# CS4398_DAC.net
KiCad netlist of a schematic drawn in Altium Designer
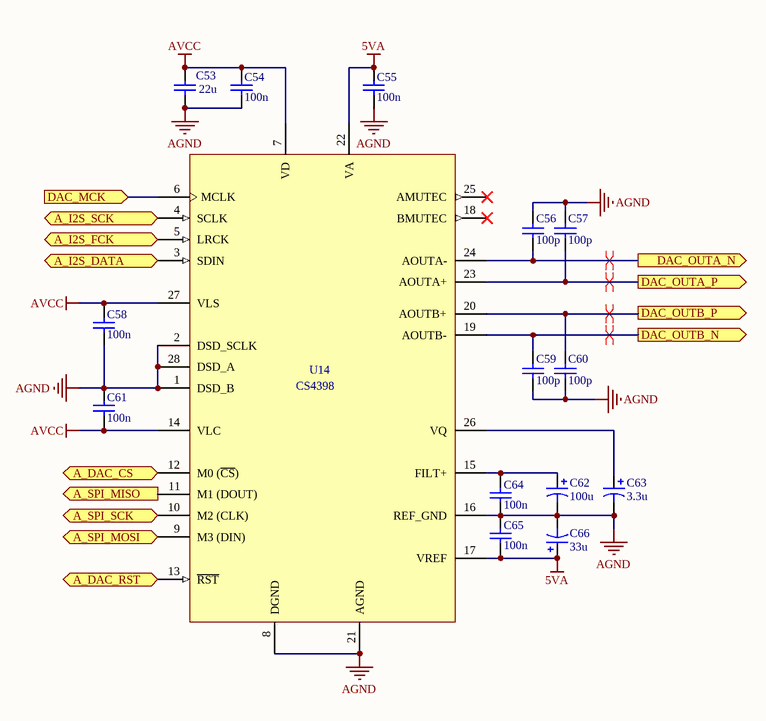
[diagram p0: CS4398_DAC.SchDoc]

(export (version "E")
  (design (tool "Eeschema 10.0.6"))
  (components
    (comp (ref "C53")
      (value "22u")
      (footprint "PCB-rf0pzaa82dpbeu9l4sxm-1")
      (description "Generic Capacitor 0603")
      (fields (field (name "LCSC PART #") "C59461") (field (name "LCSC PART #_1") "C25804"))
      (libsource (lib "CommunityVault") (part "SYM-x8hddryxw4o380xfi98v-1"))
    )
    (comp (ref "C54")
      (value "100n")
      (footprint "PCB-rf0pzaa82dpbeu9l4sxm-1")
      (description "Generic Capacitor 0603")
      (fields (field (name "LCSC PART #") "C14663") (field (name "LCSC PART #_1") "C109474"))
      (libsource (lib "FavoritesLibrary") (part "SYM-x8hddryxw4o380xfi98v-1"))
    )
    (comp (ref "C55")
      (value "100n")
      (footprint "PCB-rf0pzaa82dpbeu9l4sxm-1")
      (description "Generic Capacitor 0603")
      (fields (field (name "LCSC PART #") "C14663") (field (name "LCSC PART #_1") "C109474"))
      (libsource (lib "FavoritesLibrary") (part "SYM-x8hddryxw4o380xfi98v-1"))
    )
    (comp (ref "C56")
      (value "100p")
      (footprint "C0402_B")
      (description "0402 1 uF 10 V ±10 % Tolerance X5R SMT Multilayer Ceramic Capacitor")
      (fields
        (field (name "MANUFACTURER PART NUMBER") "CC0402KRX5R6BB105")
        (field (name "LCSC PART #") "C1546")
      )
      (libsource (lib "CommunityVault") (part "CAP-NP-2"))
    )
    (comp (ref "C57")
      (value "100p")
      (footprint "C0402_B")
      (description "0402 1 uF 10 V ±10 % Tolerance X5R SMT Multilayer Ceramic Capacitor")
      (fields
        (field (name "MANUFACTURER PART NUMBER") "CC0402KRX5R6BB105")
        (field (name "LCSC PART #") "C1546")
      )
      (libsource (lib "CommunityVault") (part "CAP-NP-2"))
    )
    (comp (ref "C58")
      (value "100n")
      (footprint "PCB-rf0pzaa82dpbeu9l4sxm-1")
      (description "Generic Capacitor 0603")
      (fields (field (name "LCSC PART #") "C14663") (field (name "LCSC PART #_1") "C109474"))
      (libsource (lib "FavoritesLibrary") (part "SYM-x8hddryxw4o380xfi98v-1"))
    )
    (comp (ref "C59")
      (value "100p")
      (footprint "C0402_B")
      (description "0402 1 uF 10 V ±10 % Tolerance X5R SMT Multilayer Ceramic Capacitor")
      (fields
        (field (name "MANUFACTURER PART NUMBER") "CC0402KRX5R6BB105")
        (field (name "LCSC PART #") "C1546")
      )
      (libsource (lib "CommunityVault") (part "CAP-NP-2"))
    )
    (comp (ref "C60")
      (value "100p")
      (footprint "C0402_B")
      (description "0402 1 uF 10 V ±10 % Tolerance X5R SMT Multilayer Ceramic Capacitor")
      (fields
        (field (name "MANUFACTURER PART NUMBER") "CC0402KRX5R6BB105")
        (field (name "LCSC PART #") "C1546")
      )
      (libsource (lib "CommunityVault") (part "CAP-NP-2"))
    )
    (comp (ref "C61")
      (value "100n")
      (footprint "PCB-rf0pzaa82dpbeu9l4sxm-1")
      (description "Generic Capacitor 0603")
      (fields (field (name "LCSC PART #") "C14663") (field (name "LCSC PART #_1") "C109474"))
      (libsource (lib "FavoritesLibrary") (part "SYM-x8hddryxw4o380xfi98v-1"))
    )
    (comp (ref "C62")
      (value "100u")
      (footprint "PCB-9bfrndi9huxo1n7cihpl-1")
      (description "In a Pack of 25, KEMET 100?F Electrolytic Capacitor 10V dc Through Hole - A758EK107M1AAAE016")
      (fields (field (name "MANUFACTURER PART NUMBER") "A758EK107M1AAAE016"))
      (libsource (lib "FavoritesLibrary") (part "SYM-6546a831a81eba81-3"))
    )
    (comp (ref "C63")
      (value "3.3u")
      (footprint "PCB-3kuidc2n9u2t7zucpvy0-1")
      (description "Cap Tant Solid 10uF 10V B CASE 10% (3.5 X 2.8 X 1.9mm) Inward L SMD 3528-21 2.5 Ohm 125C T/R")
      (fields (field (name "MANUFACTURER PART NUMBER") "TAJB106K010RNJ"))
      (libsource (lib "CommunityVault") (part "SYM-e4c92dfab4043b0e-1"))
    )
    (comp (ref "C64")
      (value "100n")
      (footprint "PCB-rf0pzaa82dpbeu9l4sxm-1")
      (description "Generic Capacitor 0603")
      (fields (field (name "LCSC PART #") "C14663") (field (name "LCSC PART #_1") "C109474"))
      (libsource (lib "FavoritesLibrary") (part "SYM-x8hddryxw4o380xfi98v-1"))
    )
    (comp (ref "C65")
      (value "100n")
      (footprint "PCB-rf0pzaa82dpbeu9l4sxm-1")
      (description "Generic Capacitor 0603")
      (fields (field (name "LCSC PART #") "C14663") (field (name "LCSC PART #_1") "C109474"))
      (libsource (lib "FavoritesLibrary") (part "SYM-x8hddryxw4o380xfi98v-1"))
    )
    (comp (ref "C66")
      (value "33u")
      (footprint "PCB-3kuidc2n9u2t7zucpvy0-1")
      (description "Cap Tant Solid 10uF 10V B CASE 10% (3.5 X 2.8 X 1.9mm) Inward L SMD 3528-21 2.5 Ohm 125C T/R")
      (fields (field (name "MANUFACTURER PART NUMBER") "TAJB106K010RNJ"))
      (libsource (lib "CommunityVault") (part "SYM-e4c92dfab4043b0e-1"))
    )
    (comp (ref "U14")
      (value "CS4398")
      (footprint "PCB-b46ddvbc1rxbl1gahzd1-1")
      (description "DAC 2-CH Delta-Sigma 24-bit 28-Pin TSSOP Rail")
      (fields (field (name "MANUFACTURER PART NUMBER") "CS4398-CZZ"))
      (libsource (lib "FavoritesLibrary") (part "SYM-031cca108660dcdb-1"))
    )
  )
  (nets
    (net (code "1") (name "/A_DAC_CS") (class "Default")
      (node (ref "U14") (pin "12") (pinfunction "M0_(~{CS})_12") (pintype "passive"))
    )
    (net (code "2") (name "/A_DAC_RST") (class "Default")
      (node (ref "U14") (pin "13") (pinfunction "~{RST}_13") (pintype "input"))
    )
    (net (code "3") (name "/A_I2S_DATA") (class "Default")
      (node (ref "U14") (pin "3") (pinfunction "SDIN_3") (pintype "input"))
    )
    (net (code "4") (name "/A_I2S_FCK") (class "Default")
      (node (ref "U14") (pin "5") (pinfunction "LRCK_5") (pintype "input"))
    )
    (net (code "5") (name "/A_I2S_SCK") (class "Default")
      (node (ref "U14") (pin "4") (pinfunction "SCLK_4") (pintype "input"))
    )
    (net (code "6") (name "/A_SPI_MISO") (class "Default")
      (node (ref "U14") (pin "11") (pinfunction "M1_(DOUT)_11") (pintype "passive"))
    )
    (net (code "7") (name "/A_SPI_MOSI") (class "Default")
      (node (ref "U14") (pin "9") (pinfunction "M3_(DIN)_9") (pintype "passive"))
    )
    (net (code "8") (name "/A_SPI_SCK") (class "Default")
      (node (ref "U14") (pin "10") (pinfunction "M2_(CLK)_10") (pintype "passive"))
    )
    (net (code "9") (name "/DAC_MCK") (class "Default")
      (node (ref "U14") (pin "6") (pinfunction "MCLK_6") (pintype "passive"))
    )
    (net (code "10") (name "/DAC_OUTA_N") (class "Default")
      (node (ref "C56") (pin "2") (pinfunction "2_2") (pintype "passive"))
      (node (ref "U14") (pin "24") (pinfunction "AOUTA-_24") (pintype "passive"))
    )
    (net (code "11") (name "/DAC_OUTA_P") (class "Default")
      (node (ref "C57") (pin "2") (pinfunction "2_2") (pintype "passive"))
      (node (ref "U14") (pin "23") (pinfunction "AOUTA+_23") (pintype "passive"))
    )
    (net (code "12") (name "/DAC_OUTB_N") (class "Default")
      (node (ref "C59") (pin "1") (pinfunction "1_1") (pintype "passive"))
      (node (ref "U14") (pin "19") (pinfunction "AOUTB-_19") (pintype "passive"))
    )
    (net (code "13") (name "/DAC_OUTB_P") (class "Default")
      (node (ref "C60") (pin "1") (pinfunction "1_1") (pintype "passive"))
      (node (ref "U14") (pin "20") (pinfunction "AOUTB+_20") (pintype "passive"))
    )
    (net (code "14") (name "5VA") (class "Default")
      (node (ref "C55") (pin "1") (pinfunction "1_1") (pintype "passive"))
      (node (ref "C65") (pin "2") (pinfunction "2_2") (pintype "passive"))
      (node (ref "C66") (pin "1") (pinfunction "1_1") (pintype "passive"))
      (node (ref "U14") (pin "17") (pinfunction "VREF_17") (pintype "passive"))
      (node (ref "U14") (pin "22") (pinfunction "VA_22") (pintype "power_in"))
    )
    (net (code "15") (name "AGND") (class "Default")
      (node (ref "C53") (pin "1") (pinfunction "1_1") (pintype "passive"))
      (node (ref "C54") (pin "2") (pinfunction "2_2") (pintype "passive"))
      (node (ref "C55") (pin "2") (pinfunction "2_2") (pintype "passive"))
      (node (ref "C56") (pin "1") (pinfunction "1_1") (pintype "passive"))
      (node (ref "C57") (pin "1") (pinfunction "1_1") (pintype "passive"))
      (node (ref "C58") (pin "2") (pinfunction "2_2") (pintype "passive"))
      (node (ref "C59") (pin "2") (pinfunction "2_2") (pintype "passive"))
      (node (ref "C60") (pin "2") (pinfunction "2_2") (pintype "passive"))
      (node (ref "C61") (pin "1") (pinfunction "1_1") (pintype "passive"))
      (node (ref "C62") (pin "2") (pinfunction "2_2") (pintype "passive"))
      (node (ref "C63") (pin "2") (pinfunction "2_2") (pintype "passive"))
      (node (ref "C64") (pin "2") (pinfunction "2_2") (pintype "passive"))
      (node (ref "C65") (pin "1") (pinfunction "1_1") (pintype "passive"))
      (node (ref "C66") (pin "2") (pinfunction "2_2") (pintype "passive"))
      (node (ref "U14") (pin "1") (pinfunction "DSD_B_1") (pintype "passive"))
      (node (ref "U14") (pin "16") (pinfunction "REF_GND_16") (pintype "passive"))
      (node (ref "U14") (pin "2") (pinfunction "DSD_SCLK_2") (pintype "passive"))
      (node (ref "U14") (pin "21") (pinfunction "AGND_21") (pintype "power_in"))
      (node (ref "U14") (pin "28") (pinfunction "DSD_A_28") (pintype "passive"))
      (node (ref "U14") (pin "8") (pinfunction "DGND_8") (pintype "power_in"))
    )
    (net (code "16") (name "AVCC") (class "Default")
      (node (ref "C53") (pin "2") (pinfunction "2_2") (pintype "passive"))
      (node (ref "C54") (pin "1") (pinfunction "1_1") (pintype "passive"))
      (node (ref "C58") (pin "1") (pinfunction "1_1") (pintype "passive"))
      (node (ref "C61") (pin "2") (pinfunction "2_2") (pintype "passive"))
      (node (ref "U14") (pin "14") (pinfunction "VLC_14") (pintype "passive"))
      (node (ref "U14") (pin "27") (pinfunction "VLS_27") (pintype "passive"))
      (node (ref "U14") (pin "7") (pinfunction "VD_7") (pintype "power_in"))
    )
    (net (code "17") (name "Net-(U14-FILT+)") (class "Default")
      (node (ref "C62") (pin "1") (pinfunction "1_1") (pintype "passive"))
      (node (ref "C64") (pin "1") (pinfunction "1_1") (pintype "passive"))
      (node (ref "U14") (pin "15") (pinfunction "FILT+_15") (pintype "passive"))
    )
    (net (code "18") (name "Net-(U14-VQ)") (class "Default")
      (node (ref "C63") (pin "1") (pinfunction "1_1") (pintype "passive"))
      (node (ref "U14") (pin "26") (pinfunction "VQ_26") (pintype "passive"))
    )
    (net (code "19") (name "unconnected-(U14-AMUTEC-Pad25)") (class "Default")
      (node (ref "U14") (pin "25") (pinfunction "AMUTEC_25") (pintype "output+no_connect"))
    )
    (net (code "20") (name "unconnected-(U14-BMUTEC-Pad18)") (class "Default")
      (node (ref "U14") (pin "18") (pinfunction "BMUTEC_18") (pintype "output+no_connect"))
    )
  )
)
